# mega.net
KiCad netlist of a schematic drawn in EAGLE
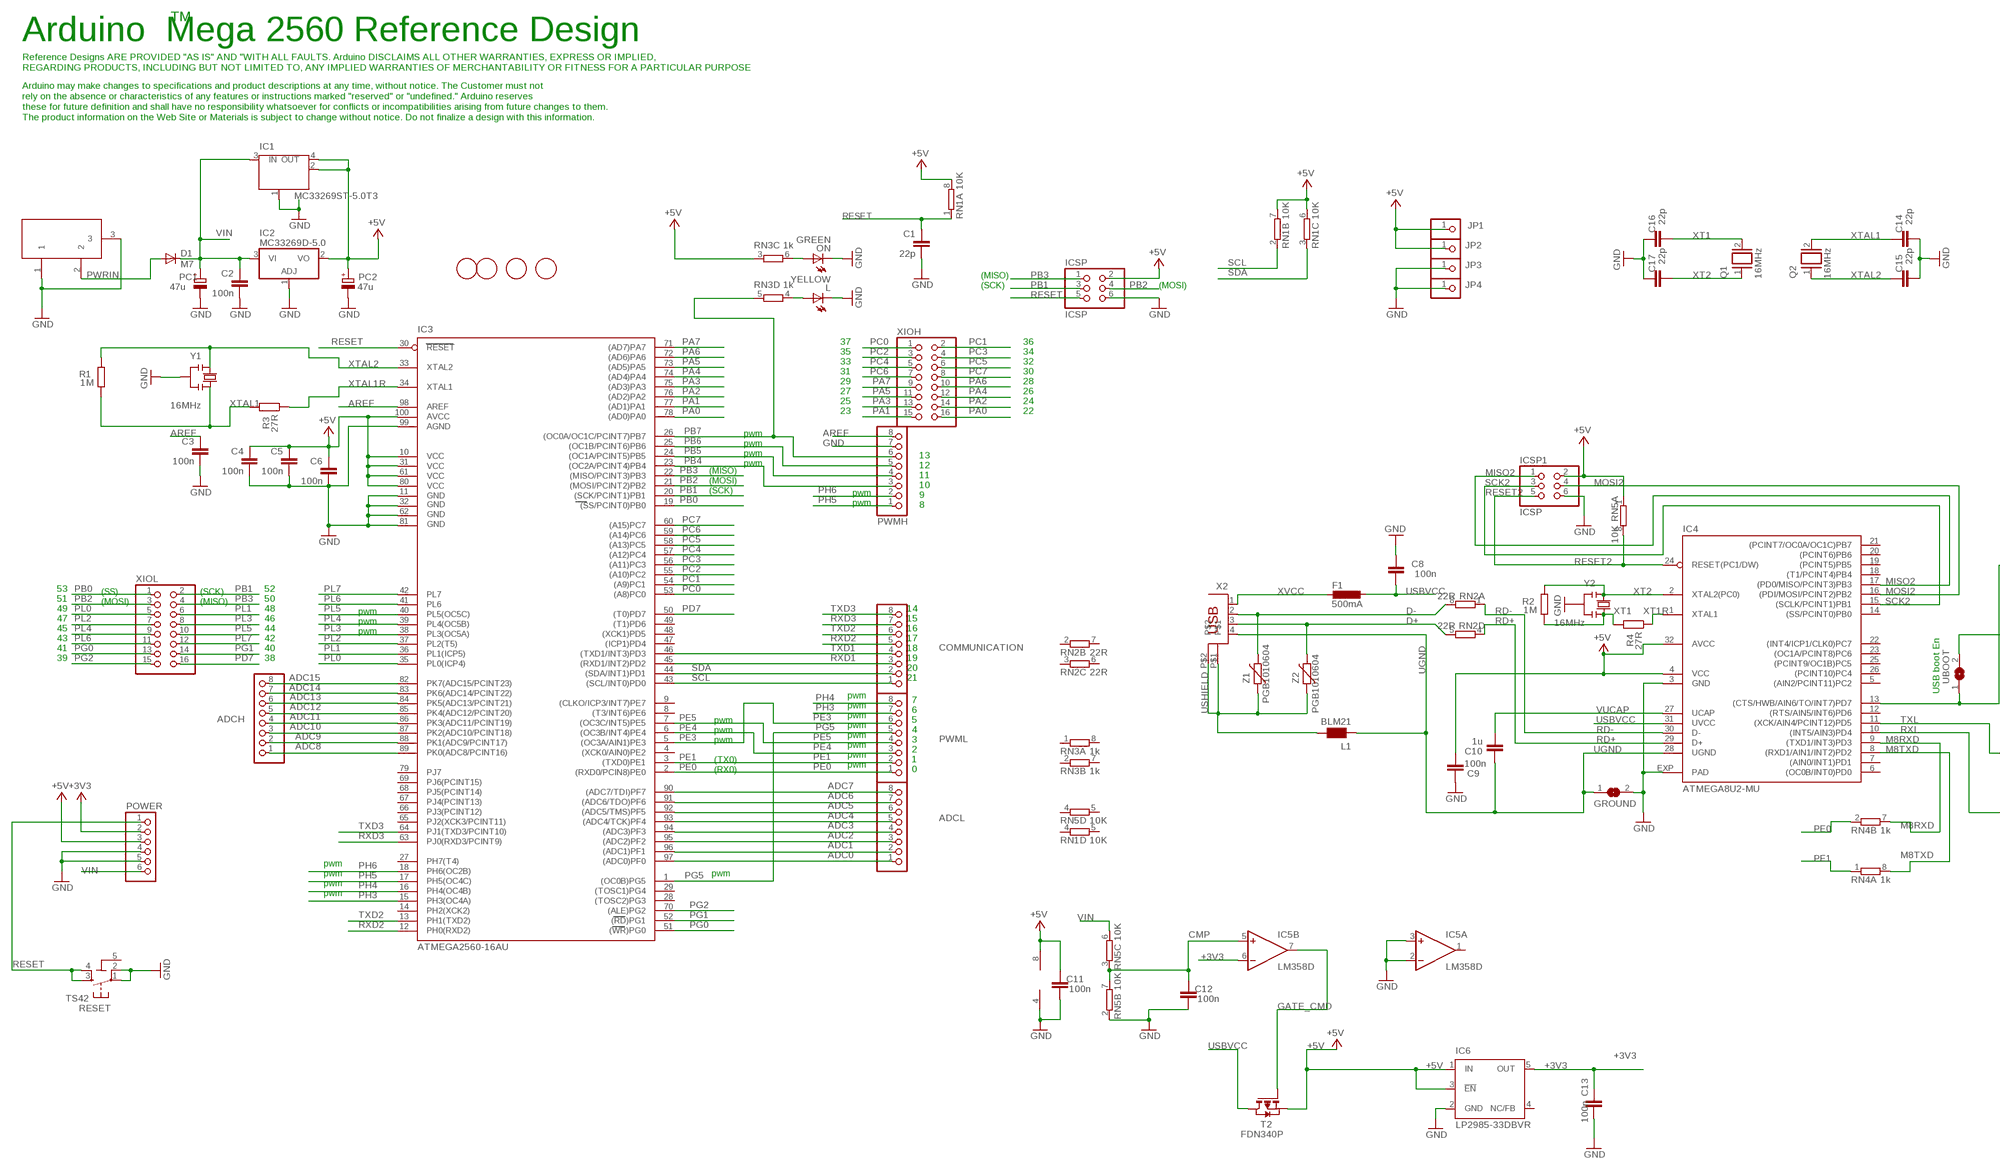
[diagram p0: schematic, sheet 1, part 1 of 2]
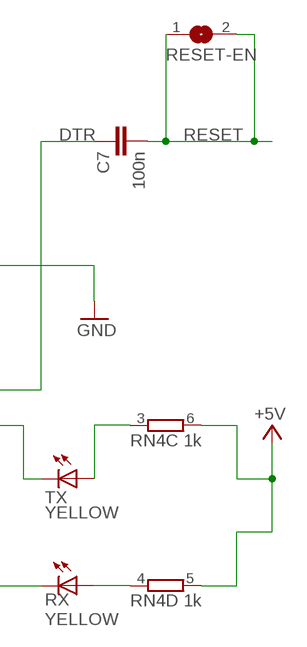
[diagram p1: schematic, sheet 1, part 2 of 2]

(export (version "E")
  (design (tool "Eeschema 10.0.6"))
  (components
    (comp (ref "ADCH")
      (value "PINHD-1X8")
      (footprint "eagle-import:1X08")
      (libsource (lib "eagle-import") (part "PINHD-1X8"))
    )
    (comp (ref "ADCL")
      (value "PINHD-1X8")
      (footprint "eagle-import:1X08")
      (libsource (lib "eagle-import") (part "PINHD-1X8"))
    )
    (comp (ref "C1")
      (value "22p")
      (footprint "eagle-import:C0603-ROUND")
      (libsource (lib "eagle-import") (part "C-EU0603-RND"))
    )
    (comp (ref "C2")
      (value "100n")
      (footprint "eagle-import:C0603-ROUND")
      (libsource (lib "eagle-import") (part "C-EU0603-RND"))
    )
    (comp (ref "C3")
      (value "100n")
      (footprint "eagle-import:C0603-ROUND")
      (libsource (lib "eagle-import") (part "C-EU0603-RND"))
    )
    (comp (ref "C4")
      (value "100n")
      (footprint "eagle-import:C0603-ROUND")
      (libsource (lib "eagle-import") (part "C-EU0603-RND"))
    )
    (comp (ref "C5")
      (value "100n")
      (footprint "eagle-import:C0603-ROUND")
      (libsource (lib "eagle-import") (part "C-EU0603-RND"))
    )
    (comp (ref "C6")
      (value "100n")
      (footprint "eagle-import:C0603-ROUND")
      (libsource (lib "eagle-import") (part "C-EU0603-RND"))
    )
    (comp (ref "C7")
      (value "100n")
      (footprint "eagle-import:C0603-ROUND")
      (libsource (lib "eagle-import") (part "C-EU0603-RND"))
    )
    (comp (ref "C8")
      (value "100n")
      (footprint "eagle-import:C0603")
      (libsource (lib "eagle-import") (part "rcl_C-EUC0603"))
    )
    (comp (ref "C9")
      (value "100n")
      (footprint "eagle-import:C0603-ROUND")
      (libsource (lib "eagle-import") (part "C-EU0603-RND"))
    )
    (comp (ref "C10")
      (value "1u")
      (footprint "eagle-import:C0603-ROUND")
      (libsource (lib "eagle-import") (part "C-EU0603-RND"))
    )
    (comp (ref "C11")
      (value "100n")
      (footprint "eagle-import:C0603")
      (libsource (lib "eagle-import") (part "rcl_C-EUC0603"))
    )
    (comp (ref "C12")
      (value "100n")
      (footprint "eagle-import:C0603-ROUND")
      (libsource (lib "eagle-import") (part "C-EU0603-RND"))
    )
    (comp (ref "C13")
      (value "100n")
      (footprint "eagle-import:C0603-ROUND")
      (libsource (lib "eagle-import") (part "C-EU0603-RND"))
    )
    (comp (ref "C14")
      (value "22p")
      (footprint "eagle-import:C0603-ROUND")
      (libsource (lib "eagle-import") (part "C-EU0603-RND"))
    )
    (comp (ref "C15")
      (value "22p")
      (footprint "eagle-import:C0603-ROUND")
      (libsource (lib "eagle-import") (part "C-EU0603-RND"))
    )
    (comp (ref "C16")
      (value "22p")
      (footprint "eagle-import:C0603-ROUND")
      (libsource (lib "eagle-import") (part "C-EU0603-RND"))
    )
    (comp (ref "C17")
      (value "22p")
      (footprint "eagle-import:C0603-ROUND")
      (libsource (lib "eagle-import") (part "C-EU0603-RND"))
    )
    (comp (ref "COMMUNICATION")
      (value "PINHD-1X8")
      (footprint "eagle-import:1X08")
      (libsource (lib "eagle-import") (part "PINHD-1X8"))
    )
    (comp (ref "D1")
      (value "M7")
      (footprint "eagle-import:SMB")
      (libsource (lib "eagle-import") (part "DIODE-SMB"))
    )
    (comp (ref "F1")
      (value "500mA")
      (footprint "eagle-import:L1812")
      (libsource (lib "eagle-import") (part "L-EUL1812"))
    )
    (comp (ref "GROUND")
      (value "SJ")
      (footprint "eagle-import:SJ")
      (libsource (lib "eagle-import") (part "SJ"))
    )
    (comp (ref "IC1")
      (value "MC33269ST-5.0T3")
      (footprint "eagle-import:SOT223")
      (libsource (lib "eagle-import") (part "MC33269ST-3.3T3"))
    )
    (comp (ref "IC2")
      (value "MC33269D-5.0")
      (footprint "eagle-import:DPACK")
      (libsource (lib "eagle-import") (part "MC33269?D-5.0"))
    )
    (comp (ref "IC3")
      (value "ATMEGA2560-16AU")
      (footprint "eagle-import:TQFP100")
      (libsource (lib "eagle-import") (part "ATMEGAAU1280-16"))
    )
    (comp (ref "IC4")
      (value "ATMEGA8U2-MU")
      (footprint "eagle-import:QFN32")
      (libsource (lib "eagle-import") (part "ATMEGA8U2-MU"))
    )
    (comp (ref "IC5")
      (value "LM358D")
      (footprint "eagle-import:SO08")
      (libsource (lib "eagle-import") (part "LM358D"))
    )
    (comp (ref "IC6")
      (value "LP2985-33DBVR")
      (footprint "eagle-import:SOT23-DBV")
      (libsource (lib "eagle-import") (part "TPS77033"))
    )
    (comp (ref "ICSP")
      (value "ICSP")
      (footprint "eagle-import:2X03")
      (libsource (lib "eagle-import") (part "PINHD-2X3"))
    )
    (comp (ref "ICSP1")
      (value "ICSP")
      (footprint "eagle-import:2X03")
      (libsource (lib "eagle-import") (part "PINHD-2X3"))
    )
    (comp (ref "JP1")
      (value "PINHD-1X1")
      (footprint "eagle-import:1X01")
      (libsource (lib "eagle-import") (part "PINHD-1X1"))
    )
    (comp (ref "JP2")
      (value "PINHD-1X1")
      (footprint "eagle-import:1X01")
      (libsource (lib "eagle-import") (part "PINHD-1X1"))
    )
    (comp (ref "JP3")
      (value "PINHD-1X1")
      (footprint "eagle-import:1X01")
      (libsource (lib "eagle-import") (part "PINHD-1X1"))
    )
    (comp (ref "JP4")
      (value "PINHD-1X1")
      (footprint "eagle-import:1X01")
      (libsource (lib "eagle-import") (part "PINHD-1X1"))
    )
    (comp (ref "L")
      (value "YELLOW")
      (footprint "eagle-import:CHIP-LED0805")
      (libsource (lib "eagle-import") (part "LEDCHIP-LED0805"))
    )
    (comp (ref "L1")
      (value "BLM21")
      (footprint "eagle-import:0805")
      (libsource (lib "eagle-import") (part "WE-CBF_0805"))
    )
    (comp (ref "ON")
      (value "GREEN")
      (footprint "eagle-import:CHIP-LED0805")
      (libsource (lib "eagle-import") (part "LEDCHIP-LED0805"))
    )
    (comp (ref "PC1")
      (value "47u")
      (footprint "eagle-import:PANASONIC_D")
      (libsource (lib "eagle-import") (part "CPOL-EUD"))
    )
    (comp (ref "PC2")
      (value "47u")
      (footprint "eagle-import:PANASONIC_D")
      (libsource (lib "eagle-import") (part "CPOL-EUD"))
    )
    (comp (ref "POWER")
      (value "PINHD-1X6")
      (footprint "eagle-import:1X06")
      (libsource (lib "eagle-import") (part "PINHD-1X6"))
    )
    (comp (ref "PWMH")
      (value "PINHD-1X8")
      (footprint "eagle-import:1X08")
      (libsource (lib "eagle-import") (part "PINHD-1X8"))
    )
    (comp (ref "PWML")
      (value "PINHD-1X8")
      (footprint "eagle-import:1X08")
      (libsource (lib "eagle-import") (part "PINHD-1X8"))
    )
    (comp (ref "Q1")
      (value "16MHz")
      (footprint "eagle-import:QS")
      (libsource (lib "eagle-import") (part "XTAL/S"))
    )
    (comp (ref "Q2")
      (value "16MHz")
      (footprint "eagle-import:QS")
      (libsource (lib "eagle-import") (part "XTAL/S"))
    )
    (comp (ref "R1")
      (value "1M")
      (footprint "eagle-import:R0603-ROUND")
      (libsource (lib "eagle-import") (part "R-EU_R0603"))
    )
    (comp (ref "R2")
      (value "1M")
      (footprint "eagle-import:R0603-ROUND")
      (libsource (lib "eagle-import") (part "R-EU_R0603"))
    )
    (comp (ref "R3")
      (value "27R")
      (footprint "eagle-import:R0603-ROUND")
      (libsource (lib "eagle-import") (part "R-EU_R0603"))
    )
    (comp (ref "R4")
      (value "27R")
      (footprint "eagle-import:R0603-ROUND")
      (libsource (lib "eagle-import") (part "R-EU_R0603"))
    )
    (comp (ref "RESET")
      (value "TS42")
      (footprint "eagle-import:TS42")
      (libsource (lib "eagle-import") (part "TS42"))
    )
    (comp (ref "RESET-EN")
      (value "SJ")
      (footprint "eagle-import:SJ")
      (libsource (lib "eagle-import") (part "SJ"))
    )
    (comp (ref "RN1")
      (value "10K")
      (footprint "eagle-import:CAT16")
      (libsource (lib "eagle-import") (part "4R-NCAT16"))
    )
    (comp (ref "RN2")
      (value "22R")
      (footprint "eagle-import:CAY16")
      (libsource (lib "eagle-import") (part "4R-NCAY16"))
    )
    (comp (ref "RN3")
      (value "1k")
      (footprint "eagle-import:CAY16")
      (libsource (lib "eagle-import") (part "4R-NCAY16"))
    )
    (comp (ref "RN4")
      (value "1k")
      (footprint "eagle-import:CAY16")
      (libsource (lib "eagle-import") (part "4R-NCAY16"))
    )
    (comp (ref "RN5")
      (value "10K")
      (footprint "eagle-import:CAT16")
      (libsource (lib "eagle-import") (part "4R-NCAT16"))
    )
    (comp (ref "RX")
      (value "YELLOW")
      (footprint "eagle-import:CHIP-LED0805")
      (libsource (lib "eagle-import") (part "LEDCHIP-LED0805"))
    )
    (comp (ref "T2")
      (value "FDN340P")
      (footprint "eagle-import:SOT-23")
      (libsource (lib "eagle-import") (part "PMOSSOT23"))
    )
    (comp (ref "TX")
      (value "YELLOW")
      (footprint "eagle-import:CHIP-LED0805")
      (libsource (lib "eagle-import") (part "LEDCHIP-LED0805"))
    )
    (comp (ref "U$2")
      (value "FIDUCIALMOUNT")
      (footprint "eagle-import:FIDUCIA-MOUNT")
      (libsource (lib "eagle-import") (part "FIDUCIALMOUNT"))
    )
    (comp (ref "U$3")
      (value "FIDUCIALMOUNT")
      (footprint "eagle-import:FIDUCIA-MOUNT")
      (libsource (lib "eagle-import") (part "FIDUCIALMOUNT"))
    )
    (comp (ref "U$4")
      (value "FIDUCIALMOUNT")
      (footprint "eagle-import:FIDUCIA-MOUNT")
      (libsource (lib "eagle-import") (part "FIDUCIALMOUNT"))
    )
    (comp (ref "U$5")
      (value "FIDUCIALMOUNT")
      (footprint "eagle-import:FIDUCIA-MOUNT")
      (libsource (lib "eagle-import") (part "FIDUCIALMOUNT"))
    )
    (comp (ref "UBOOT")
      (value "SJ")
      (footprint "eagle-import:SJ")
      (libsource (lib "eagle-import") (part "SJ"))
    )
    (comp (ref "X1")
      (value "DC21MMX")
      (footprint "eagle-import:DC-21MM")
      (libsource (lib "eagle-import") (part "DC21MMX"))
    )
    (comp (ref "X2")
      (value "PN61729")
      (footprint "eagle-import:PN61729")
      (libsource (lib "eagle-import") (part "PN61729"))
    )
    (comp (ref "XIOH")
      (value "PINHD-2X8")
      (footprint "eagle-import:2X08")
      (libsource (lib "eagle-import") (part "PINHD-2X8"))
    )
    (comp (ref "XIOL")
      (value "PINHD-2X8")
      (footprint "eagle-import:2X08")
      (libsource (lib "eagle-import") (part "PINHD-2X8"))
    )
    (comp (ref "Y1")
      (value "16MHz")
      (footprint "eagle-import:RESONATOR")
      (libsource (lib "eagle-import") (part "RESONATORMU"))
    )
    (comp (ref "Y2")
      (value "16MHz")
      (footprint "eagle-import:RESONATOR")
      (libsource (lib "eagle-import") (part "RESONATORMU"))
    )
    (comp (ref "Z1")
      (value "PGB1010604")
      (footprint "eagle-import:CT_CN0603")
      (libsource (lib "eagle-import") (part "VARISTORCN0603"))
    )
    (comp (ref "Z2")
      (value "PGB1010604")
      (footprint "eagle-import:CT_CN0603")
      (libsource (lib "eagle-import") (part "VARISTORCN0603"))
    )
  )
  (nets
    (net (code "1") (name "+3V3") (class "Default")
      (node (ref "C13") (pin "2") (pinfunction "2_2") (pintype "passive"))
      (node (ref "IC5") (pin "6") (pinfunction "-IN_6") (pintype "input"))
      (node (ref "IC6") (pin "5") (pinfunction "OUT_5") (pintype "passive"))
      (node (ref "POWER") (pin "2") (pinfunction "2_2") (pintype "passive"))
    )
    (net (code "2") (name "+5V") (class "Default")
      (node (ref "C11") (pin "2") (pinfunction "2_2") (pintype "passive"))
      (node (ref "C4") (pin "1") (pinfunction "1_1") (pintype "passive"))
      (node (ref "C5") (pin "1") (pinfunction "1_1") (pintype "passive"))
      (node (ref "C6") (pin "1") (pinfunction "1_1") (pintype "passive"))
      (node (ref "C9") (pin "1") (pinfunction "1_1") (pintype "passive"))
      (node (ref "IC1") (pin "2") (pinfunction "OUT_2") (pintype "passive"))
      (node (ref "IC1") (pin "4") (pinfunction "OUT_4") (pintype "passive"))
      (node (ref "IC2") (pin "2") (pinfunction "VO_2") (pintype "passive"))
      (node (ref "IC3") (pin "10") (pinfunction "VCC_10") (pintype "power_in"))
      (node (ref "IC3") (pin "100") (pinfunction "AVCC_100") (pintype "power_in"))
      (node (ref "IC3") (pin "31") (pinfunction "VCC1_31") (pintype "power_in"))
      (node (ref "IC3") (pin "61") (pinfunction "VCC2_61") (pintype "power_in"))
      (node (ref "IC3") (pin "80") (pinfunction "VCC3_80") (pintype "power_in"))
      (node (ref "IC4") (pin "32") (pinfunction "AVCC_32") (pintype "power_in"))
      (node (ref "IC4") (pin "4") (pinfunction "VCC_4") (pintype "power_in"))
      (node (ref "IC5") (pin "8") (pinfunction "V+_8") (pintype "power_in"))
      (node (ref "IC6") (pin "1") (pinfunction "IN_1") (pintype "input"))
      (node (ref "IC6") (pin "3") (pinfunction "~{EN}_3") (pintype "input"))
      (node (ref "ICSP") (pin "2") (pinfunction "2_2") (pintype "passive"))
      (node (ref "ICSP1") (pin "2") (pinfunction "2_2") (pintype "passive"))
      (node (ref "JP1") (pin "1") (pinfunction "1_1") (pintype "passive"))
      (node (ref "JP2") (pin "1") (pinfunction "1_1") (pintype "passive"))
      (node (ref "PC2") (pin "+") (pinfunction "+_+") (pintype "passive"))
      (node (ref "POWER") (pin "3") (pinfunction "3_3") (pintype "passive"))
      (node (ref "RN1") (pin "6") (pinfunction "2_6") (pintype "passive"))
      (node (ref "RN1") (pin "7") (pinfunction "2_7") (pintype "passive"))
      (node (ref "RN1") (pin "8") (pinfunction "2_8") (pintype "passive"))
      (node (ref "RN3") (pin "3") (pinfunction "1_3") (pintype "passive"))
      (node (ref "RN4") (pin "5") (pinfunction "2_5") (pintype "passive"))
      (node (ref "RN4") (pin "6") (pinfunction "2_6") (pintype "passive"))
      (node (ref "RN5") (pin "1") (pinfunction "1_1") (pintype "passive"))
      (node (ref "T2") (pin "2") (pinfunction "S_2") (pintype "passive"))
    )
    (net (code "3") (name "/5-GND") (class "Default")
      (node (ref "RESET") (pin "5") (pinfunction "5-GND_5") (pintype "power_in"))
    )
    (net (code "4") (name "/ADC0") (class "Default")
      (node (ref "ADCL") (pin "1") (pinfunction "1_1") (pintype "passive"))
      (node (ref "IC3") (pin "97") (pinfunction "(ADC0)PF0_97") (pintype "bidirectional"))
    )
    (net (code "5") (name "/ADC1") (class "Default")
      (node (ref "ADCL") (pin "2") (pinfunction "2_2") (pintype "passive"))
      (node (ref "IC3") (pin "96") (pinfunction "(ADC1)PF1_96") (pintype "bidirectional"))
    )
    (net (code "6") (name "/ADC2") (class "Default")
      (node (ref "ADCL") (pin "3") (pinfunction "3_3") (pintype "passive"))
      (node (ref "IC3") (pin "95") (pinfunction "(ADC2)PF2_95") (pintype "bidirectional"))
    )
    (net (code "7") (name "/ADC3") (class "Default")
      (node (ref "ADCL") (pin "4") (pinfunction "4_4") (pintype "passive"))
      (node (ref "IC3") (pin "94") (pinfunction "(ADC3)PF3_94") (pintype "bidirectional"))
    )
    (net (code "8") (name "/ADC4") (class "Default")
      (node (ref "ADCL") (pin "5") (pinfunction "5_5") (pintype "passive"))
      (node (ref "IC3") (pin "93") (pinfunction "(ADC4/TCK)PF4_93") (pintype "bidirectional"))
    )
    (net (code "9") (name "/ADC5") (class "Default")
      (node (ref "ADCL") (pin "6") (pinfunction "6_6") (pintype "passive"))
      (node (ref "IC3") (pin "92") (pinfunction "(ADC5/TMS)PF5_92") (pintype "bidirectional"))
    )
    (net (code "10") (name "/ADC6") (class "Default")
      (node (ref "ADCL") (pin "7") (pinfunction "7_7") (pintype "passive"))
      (node (ref "IC3") (pin "91") (pinfunction "(ADC6/TDO)PF6_91") (pintype "bidirectional"))
    )
    (net (code "11") (name "/ADC7") (class "Default")
      (node (ref "ADCL") (pin "8") (pinfunction "8_8") (pintype "passive"))
      (node (ref "IC3") (pin "90") (pinfunction "(ADC7/TDI)PF7_90") (pintype "bidirectional"))
    )
    (net (code "12") (name "/ADC8") (class "Default")
      (node (ref "ADCH") (pin "1") (pinfunction "1_1") (pintype "passive"))
      (node (ref "IC3") (pin "89") (pinfunction "PK0(ADC8/PCINT16)_89") (pintype "bidirectional"))
    )
    (net (code "13") (name "/ADC9") (class "Default")
      (node (ref "ADCH") (pin "2") (pinfunction "2_2") (pintype "passive"))
      (node (ref "IC3") (pin "88") (pinfunction "PK1(ADC9/PCINT17)_88") (pintype "bidirectional"))
    )
    (net (code "14") (name "/ADC10") (class "Default")
      (node (ref "ADCH") (pin "3") (pinfunction "3_3") (pintype "passive"))
      (node (ref "IC3") (pin "87") (pinfunction "PK2(ADC10/PCINT18)_87") (pintype "bidirectional"))
    )
    (net (code "15") (name "/ADC11") (class "Default")
      (node (ref "ADCH") (pin "4") (pinfunction "4_4") (pintype "passive"))
      (node (ref "IC3") (pin "86") (pinfunction "PK3(ADC11/PCINT19)_86") (pintype "bidirectional"))
    )
    (net (code "16") (name "/ADC12") (class "Default")
      (node (ref "ADCH") (pin "5") (pinfunction "5_5") (pintype "passive"))
      (node (ref "IC3") (pin "85") (pinfunction "PK4(ADC12/PCINT20)_85") (pintype "bidirectional"))
    )
    (net (code "17") (name "/ADC13") (class "Default")
      (node (ref "ADCH") (pin "6") (pinfunction "6_6") (pintype "passive"))
      (node (ref "IC3") (pin "84") (pinfunction "PK5(ADC13/PCINT21)_84") (pintype "bidirectional"))
    )
    (net (code "18") (name "/ADC14") (class "Default")
      (node (ref "ADCH") (pin "7") (pinfunction "7_7") (pintype "passive"))
      (node (ref "IC3") (pin "83") (pinfunction "PK6(ADC14/PCINT22)_83") (pintype "bidirectional"))
    )
    (net (code "19") (name "/ADC15") (class "Default")
      (node (ref "ADCH") (pin "8") (pinfunction "8_8") (pintype "passive"))
      (node (ref "IC3") (pin "82") (pinfunction "PK7(ADC15/PCINT23)_82") (pintype "bidirectional"))
    )
    (net (code "20") (name "/AREF") (class "Default")
      (node (ref "C3") (pin "1") (pinfunction "1_1") (pintype "passive"))
      (node (ref "IC3") (pin "98") (pinfunction "AREF_98") (pintype "bidirectional"))
      (node (ref "PWMH") (pin "8") (pinfunction "8_8") (pintype "passive"))
    )
    (net (code "21") (name "/CMP") (class "Default")
      (node (ref "C12") (pin "2") (pinfunction "2_2") (pintype "passive"))
      (node (ref "IC5") (pin "5") (pinfunction "+IN_5") (pintype "input"))
      (node (ref "RN5") (pin "3") (pinfunction "1_3") (pintype "passive"))
      (node (ref "RN5") (pin "7") (pinfunction "2_7") (pintype "passive"))
    )
    (net (code "22") (name "/D+") (class "Default")
      (node (ref "RN2") (pin "5") (pinfunction "2_5") (pintype "passive"))
      (node (ref "X2") (pin "3") (pinfunction "3_3") (pintype "bidirectional"))
      (node (ref "Z2") (pin "2") (pinfunction "2_2") (pintype "passive"))
    )
    (net (code "23") (name "/D-") (class "Default")
      (node (ref "RN2") (pin "8") (pinfunction "2_8") (pintype "passive"))
      (node (ref "X2") (pin "2") (pinfunction "2_2") (pintype "bidirectional"))
      (node (ref "Z1") (pin "2") (pinfunction "2_2") (pintype "passive"))
    )
    (net (code "24") (name "/DTR") (class "Default")
      (node (ref "C7") (pin "1") (pinfunction "1_1") (pintype "passive"))
      (node (ref "IC4") (pin "13") (pinfunction "(CTS/HWB/AIN6/TO/INT7)PD7_13") (pintype "bidirectional"))
      (node (ref "UBOOT") (pin "1") (pinfunction "1_1") (pintype "passive"))
    )
    (net (code "25") (name "/GATE_CMD") (class "Default")
      (node (ref "IC5") (pin "7") (pinfunction "OUT_7") (pintype "output"))
      (node (ref "T2") (pin "3") (pinfunction "G_3") (pintype "passive"))
    )
    (net (code "26") (name "/M8RXD") (class "Default")
      (node (ref "IC4") (pin "9") (pinfunction "(TXD1/INT3)PD3_9") (pintype "bidirectional"))
      (node (ref "RN4") (pin "7") (pinfunction "2_7") (pintype "passive"))
    )
    (net (code "27") (name "/M8TXD") (class "Default")
      (node (ref "IC4") (pin "8") (pinfunction "(RXD1/AIN1/INT2)PD2_8") (pintype "bidirectional"))
      (node (ref "RN4") (pin "8") (pinfunction "2_8") (pintype "passive"))
    )
    (net (code "28") (name "/MISO2") (class "Default")
      (node (ref "IC4") (pin "17") (pinfunction "(PD0/MISO/PCINT3)PB3_17") (pintype "bidirectional"))
      (node (ref "ICSP1") (pin "1") (pinfunction "1_1") (pintype "passive"))
    )
    (net (code "29") (name "/MOSI2") (class "Default")
      (node (ref "IC4") (pin "16") (pinfunction "(PDI/MOSI/PCINT2)PB2_16") (pintype "bidirectional"))
      (node (ref "ICSP1") (pin "4") (pinfunction "4_4") (pintype "passive"))
    )
    (net (code "30") (name "/PA0") (class "Default")
      (node (ref "IC3") (pin "78") (pinfunction "(AD0)PA0_78") (pintype "bidirectional"))
      (node (ref "XIOH") (pin "16") (pinfunction "16_16") (pintype "passive"))
    )
    (net (code "31") (name "/PA1") (class "Default")
      (node (ref "IC3") (pin "77") (pinfunction "(AD1)PA1_77") (pintype "bidirectional"))
      (node (ref "XIOH") (pin "15") (pinfunction "15_15") (pintype "passive"))
    )
    (net (code "32") (name "/PA2") (class "Default")
      (node (ref "IC3") (pin "76") (pinfunction "(AD2)PA2_76") (pintype "bidirectional"))
      (node (ref "XIOH") (pin "14") (pinfunction "14_14") (pintype "passive"))
    )
    (net (code "33") (name "/PA3") (class "Default")
      (node (ref "IC3") (pin "75") (pinfunction "(AD3)PA3_75") (pintype "bidirectional"))
      (node (ref "XIOH") (pin "13") (pinfunction "13_13") (pintype "passive"))
    )
    (net (code "34") (name "/PA4") (class "Default")
      (node (ref "IC3") (pin "74") (pinfunction "(AD4)PA4_74") (pintype "bidirectional"))
      (node (ref "XIOH") (pin "12") (pinfunction "12_12") (pintype "passive"))
    )
    (net (code "35") (name "/PA5") (class "Default")
      (node (ref "IC3") (pin "73") (pinfunction "(AD5)PA5_73") (pintype "bidirectional"))
      (node (ref "XIOH") (pin "11") (pinfunction "11_11") (pintype "passive"))
    )
    (net (code "36") (name "/PA6") (class "Default")
      (node (ref "IC3") (pin "72") (pinfunction "(AD6)PA6_72") (pintype "bidirectional"))
      (node (ref "XIOH") (pin "10") (pinfunction "10_10") (pintype "passive"))
    )
    (net (code "37") (name "/PA7") (class "Default")
      (node (ref "IC3") (pin "71") (pinfunction "(AD7)PA7_71") (pintype "bidirectional"))
      (node (ref "XIOH") (pin "9") (pinfunction "9_9") (pintype "passive"))
    )
    (net (code "38") (name "/PB0") (class "Default")
      (node (ref "IC3") (pin "19") (pinfunction "(SS/PCINT0)PB0_19") (pintype "bidirectional"))
      (node (ref "XIOL") (pin "1") (pinfunction "1_1") (pintype "passive"))
    )
    (net (code "39") (name "/PB1") (class "Default")
      (node (ref "IC3") (pin "20") (pinfunction "(SCK/PCINT1)PB1_20") (pintype "bidirectional"))
      (node (ref "ICSP") (pin "3") (pinfunction "3_3") (pintype "passive"))
      (node (ref "XIOL") (pin "2") (pinfunction "2_2") (pintype "passive"))
    )
    (net (code "40") (name "/PB2") (class "Default")
      (node (ref "IC3") (pin "21") (pinfunction "(MOSI/PCINT2)PB2_21") (pintype "bidirectional"))
      (node (ref "ICSP") (pin "4") (pinfunction "4_4") (pintype "passive"))
      (node (ref "XIOL") (pin "3") (pinfunction "3_3") (pintype "passive"))
    )
    (net (code "41") (name "/PB3") (class "Default")
      (node (ref "IC3") (pin "22") (pinfunction "(MISO/PCINT3)PB3_22") (pintype "bidirectional"))
      (node (ref "ICSP") (pin "1") (pinfunction "1_1") (pintype "passive"))
      (node (ref "XIOL") (pin "4") (pinfunction "4_4") (pintype "passive"))
    )
    (net (code "42") (name "/PB4") (class "Default")
      (node (ref "IC3") (pin "23") (pinfunction "(OC2A/PCINT4)PB4_23") (pintype "bidirectional"))
      (node (ref "PWMH") (pin "3") (pinfunction "3_3") (pintype "passive"))
    )
    (net (code "43") (name "/PB5") (class "Default")
      (node (ref "IC3") (pin "24") (pinfunction "(OC1A/PCINT5)PB5_24") (pintype "bidirectional"))
      (node (ref "PWMH") (pin "4") (pinfunction "4_4") (pintype "passive"))
    )
    (net (code "44") (name "/PB6") (class "Default")
      (node (ref "IC3") (pin "25") (pinfunction "(OC1B/PCINT6)PB6_25") (pintype "bidirectional"))
      (node (ref "PWMH") (pin "5") (pinfunction "5_5") (pintype "passive"))
    )
    (net (code "45") (name "/PB7") (class "Default")
      (node (ref "IC3") (pin "26") (pinfunction "(OC0A/OC1C/PCINT7)PB7_26") (pintype "bidirectional"))
      (node (ref "PWMH") (pin "6") (pinfunction "6_6") (pintype "passive"))
      (node (ref "RN3") (pin "5") (pinfunction "2_5") (pintype "passive"))
    )
    (net (code "46") (name "/PC0") (class "Default")
      (node (ref "IC3") (pin "53") (pinfunction "(A8)PC0_53") (pintype "bidirectional"))
      (node (ref "XIOH") (pin "1") (pinfunction "1_1") (pintype "passive"))
    )
    (net (code "47") (name "/PC1") (class "Default")
      (node (ref "IC3") (pin "54") (pinfunction "(A9)PC1_54") (pintype "bidirectional"))
      (node (ref "XIOH") (pin "2") (pinfunction "2_2") (pintype "passive"))
    )
    (net (code "48") (name "/PC2") (class "Default")
      (node (ref "IC3") (pin "55") (pinfunction "(A10)PC2_55") (pintype "bidirectional"))
      (node (ref "XIOH") (pin "3") (pinfunction "3_3") (pintype "passive"))
    )
    (net (code "49") (name "/PC3") (class "Default")
      (node (ref "IC3") (pin "56") (pinfunction "(A11)PC3_56") (pintype "bidirectional"))
      (node (ref "XIOH") (pin "4") (pinfunction "4_4") (pintype "passive"))
    )
    (net (code "50") (name "/PC4") (class "Default")
      (node (ref "IC3") (pin "57") (pinfunction "(A12)PC4_57") (pintype "bidirectional"))
      (node (ref "XIOH") (pin "5") (pinfunction "5_5") (pintype "passive"))
    )
    (net (code "51") (name "/PC5") (class "Default")
      (node (ref "IC3") (pin "58") (pinfunction "(A13)PC5_58") (pintype "bidirectional"))
      (node (ref "XIOH") (pin "6") (pinfunction "6_6") (pintype "passive"))
    )
    (net (code "52") (name "/PC6") (class "Default")
      (node (ref "IC3") (pin "59") (pinfunction "(A14)PC6_59") (pintype "bidirectional"))
      (node (ref "XIOH") (pin "7") (pinfunction "7_7") (pintype "passive"))
    )
    (net (code "53") (name "/PC7") (class "Default")
      (node (ref "IC3") (pin "60") (pinfunction "(A15)PC7_60") (pintype "bidirectional"))
      (node (ref "XIOH") (pin "8") (pinfunction "8_8") (pintype "passive"))
    )
    (net (code "54") (name "/PD7") (class "Default")
      (node (ref "IC3") (pin "50") (pinfunction "(T0)PD7_50") (pintype "bidirectional"))
      (node (ref "XIOL") (pin "16") (pinfunction "16_16") (pintype "passive"))
    )
    (net (code "55") (name "/PE0") (class "Default")
      (node (ref "IC3") (pin "2") (pinfunction "(RXD0/PCIN8)PE0_2") (pintype "bidirectional"))
      (node (ref "PWML") (pin "1") (pinfunction "1_1") (pintype "passive"))
      (node (ref "RN4") (pin "2") (pinfunction "1_2") (pintype "passive"))
    )
    (net (code "56") (name "/PE1") (class "Default")
      (node (ref "IC3") (pin "3") (pinfunction "(TXD0)PE1_3") (pintype "bidirectional"))
      (node (ref "PWML") (pin "2") (pinfunction "2_2") (pintype "passive"))
      (node (ref "RN4") (pin "1") (pinfunction "1_1") (pintype "passive"))
    )
    (net (code "57") (name "/PE3") (class "Default")
      (node (ref "IC3") (pin "5") (pinfunction "(OC3A/AIN1)PE3_5") (pintype "bidirectional"))
      (node (ref "PWML") (pin "6") (pinfunction "6_6") (pintype "passive"))
    )
    (net (code "58") (name "/PE4") (class "Default")
      (node (ref "IC3") (pin "6") (pinfunction "(OC3B/INT4)PE4_6") (pintype "bidirectional"))
      (node (ref "PWML") (pin "3") (pinfunction "3_3") (pintype "passive"))
    )
    (net (code "59") (name "/PE5") (class "Default")
      (node (ref "IC3") (pin "7") (pinfunction "(OC3C/INT5)PE5_7") (pintype "bidirectional"))
      (node (ref "PWML") (pin "4") (pinfunction "4_4") (pintype "passive"))
    )
    (net (code "60") (name "/PG0") (class "Default")
      (node (ref "IC3") (pin "51") (pinfunction "(WR)PG0_51") (pintype "bidirectional"))
      (node (ref "XIOL") (pin "13") (pinfunction "13_13") (pintype "passive"))
    )
    (net (code "61") (name "/PG1") (class "Default")
      (node (ref "IC3") (pin "52") (pinfunction "(RD)PG1_52") (pintype "bidirectional"))
      (node (ref "XIOL") (pin "14") (pinfunction "14_14") (pintype "passive"))
    )
    (net (code "62") (name "/PG2") (class "Default")
      (node (ref "IC3") (pin "70") (pinfunction "(ALE)PG2_70") (pintype "bidirectional"))
      (node (ref "XIOL") (pin "15") (pinfunction "15_15") (pintype "passive"))
    )
    (net (code "63") (name "/PG5") (class "Default")
      (node (ref "IC3") (pin "1") (pinfunction "(OC0B)PG5_1") (pintype "bidirectional"))
      (node (ref "PWML") (pin "5") (pinfunction "5_5") (pintype "passive"))
    )
    (net (code "64") (name "/PH3") (class "Default")
      (node (ref "IC3") (pin "15") (pinfunction "PH3(OC4A)_15") (pintype "bidirectional"))
      (node (ref "PWML") (pin "7") (pinfunction "7_7") (pintype "passive"))
    )
    (net (code "65") (name "/PH4") (class "Default")
      (node (ref "IC3") (pin "16") (pinfunction "PH4(OC4B)_16") (pintype "bidirectional"))
      (node (ref "PWML") (pin "8") (pinfunction "8_8") (pintype "passive"))
    )
    (net (code "66") (name "/PH5") (class "Default")
      (node (ref "IC3") (pin "17") (pinfunction "PH5(OC4C)_17") (pintype "bidirectional"))
      (node (ref "PWMH") (pin "1") (pinfunction "1_1") (pintype "passive"))
    )
    (net (code "67") (name "/PH6") (class "Default")
      (node (ref "IC3") (pin "18") (pinfunction "PH6(OC2B)_18") (pintype "bidirectional"))
      (node (ref "PWMH") (pin "2") (pinfunction "2_2") (pintype "passive"))
    )
    (net (code "68") (name "/PL0") (class "Default")
      (node (ref "IC3") (pin "35") (pinfunction "PL0(ICP4)_35") (pintype "bidirectional"))
      (node (ref "XIOL") (pin "5") (pinfunction "5_5") (pintype "passive"))
    )
    (net (code "69") (name "/PL1") (class "Default")
      (node (ref "IC3") (pin "36") (pinfunction "PL1(ICP5)_36") (pintype "bidirectional"))
      (node (ref "XIOL") (pin "6") (pinfunction "6_6") (pintype "passive"))
    )
    (net (code "70") (name "/PL2") (class "Default")
      (node (ref "IC3") (pin "37") (pinfunction "PL2(T5)_37") (pintype "bidirectional"))
      (node (ref "XIOL") (pin "7") (pinfunction "7_7") (pintype "passive"))
    )
    (net (code "71") (name "/PL3") (class "Default")
      (node (ref "IC3") (pin "38") (pinfunction "PL3(OC5A)_38") (pintype "bidirectional"))
      (node (ref "XIOL") (pin "8") (pinfunction "8_8") (pintype "passive"))
    )
    (net (code "72") (name "/PL4") (class "Default")
      (node (ref "IC3") (pin "39") (pinfunction "PL4(OC5B)_39") (pintype "bidirectional"))
      (node (ref "XIOL") (pin "9") (pinfunction "9_9") (pintype "passive"))
    )
    (net (code "73") (name "/PL5") (class "Default")
      (node (ref "IC3") (pin "40") (pinfunction "PL5(OC5C)_40") (pintype "bidirectional"))
      (node (ref "XIOL") (pin "10") (pinfunction "10_10") (pintype "passive"))
    )
    (net (code "74") (name "/PL6") (class "Default")
      (node (ref "IC3") (pin "41") (pinfunction "PL6_41") (pintype "bidirectional"))
      (node (ref "XIOL") (pin "11") (pinfunction "11_11") (pintype "passive"))
    )
    (net (code "75") (name "/PL7") (class "Default")
      (node (ref "IC3") (pin "42") (pinfunction "PL7_42") (pintype "bidirectional"))
      (node (ref "XIOL") (pin "12") (pinfunction "12_12") (pintype "passive"))
    )
    (net (code "76") (name "/PWRIN") (class "Default")
      (node (ref "D1") (pin "A") (pinfunction "A_A") (pintype "passive"))
      (node (ref "X1") (pin "2") (pinfunction "2_2") (pintype "power_in"))
    )
    (net (code "77") (name "/RD+") (class "Default")
      (node (ref "IC4") (pin "29") (pinfunction "D+_29") (pintype "bidirectional"))
      (node (ref "RN2") (pin "4") (pinfunction "1_4") (pintype "passive"))
    )
    (net (code "78") (name "/RD-") (class "Default")
      (node (ref "IC4") (pin "30") (pinfunction "D-_30") (pintype "bidirectional"))
      (node (ref "RN2") (pin "1") (pinfunction "1_1") (pintype "passive"))
    )
    (net (code "79") (name "/RESET") (class "Default")
      (node (ref "C1") (pin "1") (pinfunction "1_1") (pintype "passive"))
      (node (ref "C7") (pin "2") (pinfunction "2_2") (pintype "passive"))
      (node (ref "IC3") (pin "30") (pinfunction "RESET_30") (pintype "input"))
      (node (ref "ICSP") (pin "5") (pinfunction "5_5") (pintype "passive"))
      (node (ref "POWER") (pin "1") (pinfunction "1_1") (pintype "passive"))
      (node (ref "RESET") (pin "3") (pinfunction "3_3") (pintype "passive"))
      (node (ref "RESET") (pin "4") (pinfunction "4_4") (pintype "passive"))
      (node (ref "RESET-EN") (pin "1") (pinfunction "1_1") (pintype "passive"))
      (node (ref "RESET-EN") (pin "2") (pinfunction "2_2") (pintype "passive"))
      (node (ref "RN1") (pin "1") (pinfunction "1_1") (pintype "passive"))
    )
    (net (code "80") (name "/RESET2") (class "Default")
      (node (ref "IC4") (pin "24") (pinfunction "RESET(PC1/DW)_24") (pintype "input"))
      (node (ref "ICSP1") (pin "5") (pinfunction "5_5") (pintype "passive"))
      (node (ref "RN5") (pin "8") (pinfunction "2_8") (pintype "passive"))
    )
    (net (code "81") (name "/RXD1") (class "Default")
      (node (ref "COMMUNICATION") (pin "3") (pinfunction "3_3") (pintype "passive"))
      (node (ref "IC3") (pin "45") (pinfunction "(RXD1/INT2)PD2_45") (pintype "bidirectional"))
    )
    (net (code "82") (name "/RXD2") (class "Default")
      (node (ref "COMMUNICATION") (pin "5") (pinfunction "5_5") (pintype "passive"))
      (node (ref "IC3") (pin "12") (pinfunction "PH0(RXD2)_12") (pintype "bidirectional"))
    )
    (net (code "83") (name "/RXD3") (class "Default")
      (node (ref "COMMUNICATION") (pin "7") (pinfunction "7_7") (pintype "passive"))
      (node (ref "IC3") (pin "63") (pinfunction "PJ0(RXD3/PCINT9)_63") (pintype "bidirectional"))
    )
    (net (code "84") (name "/RXL") (class "Default")
      (node (ref "IC4") (pin "10") (pinfunction "(INT5/AIN3)PD4_10") (pintype "bidirectional"))
      (node (ref "RX") (pin "C") (pinfunction "C_C") (pintype "passive"))
    )
    (net (code "85") (name "/SCK2") (class "Default")
      (node (ref "IC4") (pin "15") (pinfunction "(SCLK/PCINT1)PB1_15") (pintype "bidirectional"))
      (node (ref "ICSP1") (pin "3") (pinfunction "3_3") (pintype "passive"))
    )
    (net (code "86") (name "/SCL") (class "Default")
      (node (ref "COMMUNICATION") (pin "1") (pinfunction "1_1") (pintype "passive"))
      (node (ref "IC3") (pin "43") (pinfunction "(SCL/INT0)PD0_43") (pintype "bidirectional"))
      (node (ref "RN1") (pin "2") (pinfunction "1_2") (pintype "passive"))
    )
    (net (code "87") (name "/SDA") (class "Default")
      (node (ref "COMMUNICATION") (pin "2") (pinfunction "2_2") (pintype "passive"))
      (node (ref "IC3") (pin "44") (pinfunction "(SDA/INT1)PD1_44") (pintype "bidirectional"))
      (node (ref "RN1") (pin "3") (pinfunction "1_3") (pintype "passive"))
    )
    (net (code "88") (name "/TXD1") (class "Default")
      (node (ref "COMMUNICATION") (pin "4") (pinfunction "4_4") (pintype "passive"))
      (node (ref "IC3") (pin "46") (pinfunction "(TXD1/INT3)PD3_46") (pintype "bidirectional"))
    )
    (net (code "89") (name "/TXD2") (class "Default")
      (node (ref "COMMUNICATION") (pin "6") (pinfunction "6_6") (pintype "passive"))
      (node (ref "IC3") (pin "13") (pinfunction "PH1(TXD2)_13") (pintype "bidirectional"))
    )
    (net (code "90") (name "/TXD3") (class "Default")
      (node (ref "COMMUNICATION") (pin "8") (pinfunction "8_8") (pintype "passive"))
      (node (ref "IC3") (pin "64") (pinfunction "PJ1(TXD3/PCINT10)_64") (pintype "bidirectional"))
    )
    (net (code "91") (name "/TXL") (class "Default")
      (node (ref "IC4") (pin "11") (pinfunction "(XCK/AIN4/PCINT12)PD5_11") (pintype "bidirectional"))
      (node (ref "TX") (pin "C") (pinfunction "C_C") (pintype "passive"))
    )
    (net (code "92") (name "/UGND") (class "Default")
      (node (ref "C10") (pin "2") (pinfunction "2_2") (pintype "passive"))
      (node (ref "GROUND") (pin "1") (pinfunction "1_1") (pintype "passive"))
      (node (ref "IC4") (pin "28") (pinfunction "UGND_28") (pintype "power_in"))
      (node (ref "L1") (pin "1") (pinfunction "1_1") (pintype "passive"))
      (node (ref "X2") (pin "4") (pinfunction "4_4") (pintype "bidirectional"))
    )
    (net (code "93") (name "/USBVCC") (class "Default")
      (node (ref "C8") (pin "1") (pinfunction "1_1") (pintype "passive"))
      (node (ref "F1") (pin "1") (pinfunction "1_1") (pintype "passive"))
      (node (ref "IC4") (pin "31") (pinfunction "UVCC_31") (pintype "power_in"))
      (node (ref "T2") (pin "1") (pinfunction "D_1") (pintype "passive"))
    )
    (net (code "94") (name "/USHIELD") (class "Default")
      (node (ref "L1") (pin "2") (pinfunction "2_2") (pintype "passive"))
      (node (ref "X2") (pin "P$1") (pinfunction "P$1_P$1") (pintype "bidirectional"))
      (node (ref "X2") (pin "P$2") (pinfunction "P$2_P$2") (pintype "bidirectional"))
      (node (ref "Z1") (pin "1") (pinfunction "1_1") (pintype "passive"))
      (node (ref "Z2") (pin "1") (pinfunction "1_1") (pintype "passive"))
    )
    (net (code "95") (name "/VIN") (class "Default")
      (node (ref "C2") (pin "1") (pinfunction "1_1") (pintype "passive"))
      (node (ref "D1") (pin "C") (pinfunction "C_C") (pintype "passive"))
      (node (ref "IC1") (pin "3") (pinfunction "IN_3") (pintype "input"))
      (node (ref "IC2") (pin "3") (pinfunction "VI_3") (pintype "input"))
      (node (ref "PC1") (pin "+") (pinfunction "+_+") (pintype "passive"))
      (node (ref "POWER") (pin "6") (pinfunction "6_6") (pintype "passive"))
      (node (ref "RN5") (pin "6") (pinfunction "2_6") (pintype "passive"))
    )
    (net (code "96") (name "/VUCAP") (class "Default")
      (node (ref "C10") (pin "1") (pinfunction "1_1") (pintype "passive"))
      (node (ref "IC4") (pin "27") (pinfunction "UCAP_27") (pintype "passive"))
    )
    (net (code "97") (name "/XT1") (class "Default")
      (node (ref "C16") (pin "1") (pinfunction "1_1") (pintype "passive"))
      (node (ref "Q1") (pin "2") (pinfunction "2_2") (pintype "passive"))
      (node (ref "R2") (pin "1") (pinfunction "1_1") (pintype "passive"))
      (node (ref "R4") (pin "2") (pinfunction "2_2") (pintype "passive"))
      (node (ref "Y2") (pin "3") (pinfunction "3_3") (pintype "passive"))
    )
    (net (code "98") (name "/XT1R") (class "Default")
      (node (ref "IC4") (pin "1") (pinfunction "XTAL1_1") (pintype "bidirectional"))
      (node (ref "R4") (pin "1") (pinfunction "1_1") (pintype "passive"))
    )
    (net (code "99") (name "/XT2") (class "Default")
      (node (ref "C17") (pin "1") (pinfunction "1_1") (pintype "passive"))
      (node (ref "IC4") (pin "2") (pinfunction "XTAL2(PC0)_2") (pintype "bidirectional"))
      (node (ref "Q1") (pin "1") (pinfunction "1_1") (pintype "passive"))
      (node (ref "R2") (pin "2") (pinfunction "2_2") (pintype "passive"))
      (node (ref "Y2") (pin "1") (pinfunction "1_1") (pintype "passive"))
    )
    (net (code "100") (name "/XTAL1") (class "Default")
      (node (ref "C14") (pin "2") (pinfunction "2_2") (pintype "passive"))
      (node (ref "Q2") (pin "2") (pinfunction "2_2") (pintype "passive"))
      (node (ref "R1") (pin "1") (pinfunction "1_1") (pintype "passive"))
      (node (ref "R3") (pin "2") (pinfunction "2_2") (pintype "passive"))
      (node (ref "Y1") (pin "3") (pinfunction "3_3") (pintype "passive"))
    )
    (net (code "101") (name "/XTAL1R") (class "Default")
      (node (ref "IC3") (pin "34") (pinfunction "XTAL1_34") (pintype "input"))
      (node (ref "R3") (pin "1") (pinfunction "1_1") (pintype "passive"))
    )
    (net (code "102") (name "/XTAL2") (class "Default")
      (node (ref "C15") (pin "2") (pinfunction "2_2") (pintype "passive"))
      (node (ref "IC3") (pin "33") (pinfunction "XTAL2_33") (pintype "output"))
      (node (ref "Q2") (pin "1") (pinfunction "1_1") (pintype "passive"))
      (node (ref "R1") (pin "2") (pinfunction "2_2") (pintype "passive"))
      (node (ref "Y1") (pin "1") (pinfunction "1_1") (pintype "passive"))
    )
    (net (code "103") (name "/XVCC") (class "Default")
      (node (ref "F1") (pin "2") (pinfunction "2_2") (pintype "passive"))
      (node (ref "X2") (pin "1") (pinfunction "1_1") (pintype "bidirectional"))
    )
    (net (code "104") (name "GND") (class "Default")
      (node (ref "C1") (pin "2") (pinfunction "2_2") (pintype "passive"))
      (node (ref "C11") (pin "1") (pinfunction "1_1") (pintype "passive"))
      (node (ref "C12") (pin "1") (pinfunction "1_1") (pintype "passive"))
      (node (ref "C13") (pin "1") (pinfunction "1_1") (pintype "passive"))
      (node (ref "C14") (pin "1") (pinfunction "1_1") (pintype "passive"))
      (node (ref "C15") (pin "1") (pinfunction "1_1") (pintype "passive"))
      (node (ref "C16") (pin "2") (pinfunction "2_2") (pintype "passive"))
      (node (ref "C17") (pin "2") (pinfunction "2_2") (pintype "passive"))
      (node (ref "C2") (pin "2") (pinfunction "2_2") (pintype "passive"))
      (node (ref "C3") (pin "2") (pinfunction "2_2") (pintype "passive"))
      (node (ref "C4") (pin "2") (pinfunction "2_2") (pintype "passive"))
      (node (ref "C5") (pin "2") (pinfunction "2_2") (pintype "passive"))
      (node (ref "C6") (pin "2") (pinfunction "2_2") (pintype "passive"))
      (node (ref "C8") (pin "2") (pinfunction "2_2") (pintype "passive"))
      (node (ref "C9") (pin "2") (pinfunction "2_2") (pintype "passive"))
      (node (ref "GROUND") (pin "2") (pinfunction "2_2") (pintype "passive"))
      (node (ref "IC1") (pin "1") (pinfunction "GND/ADJ_1") (pintype "input"))
      (node (ref "IC2") (pin "1") (pinfunction "ADJ_1") (pintype "input"))
      (node (ref "IC3") (pin "11") (pinfunction "GND_11") (pintype "power_in"))
      (node (ref "IC3") (pin "32") (pinfunction "GND1_32") (pintype "power_in"))
      (node (ref "IC3") (pin "62") (pinfunction "GND2_62") (pintype "power_in"))
      (node (ref "IC3") (pin "81") (pinfunction "GND3_81") (pintype "power_in"))
      (node (ref "IC3") (pin "99") (pinfunction "AGND_99") (pintype "power_in"))
      (node (ref "IC4") (pin "3") (pinfunction "GND_3") (pintype "power_in"))
      (node (ref "IC4") (pin "EXP") (pinfunction "PAD_EXP") (pintype "power_in"))
      (node (ref "IC5") (pin "2") (pinfunction "-IN_2") (pintype "input"))
      (node (ref "IC5") (pin "3") (pinfunction "+IN_3") (pintype "input"))
      (node (ref "IC5") (pin "4") (pinfunction "V-_4") (pintype "power_in"))
      (node (ref "IC6") (pin "2") (pinfunction "GND_2") (pintype "power_in"))
      (node (ref "ICSP") (pin "6") (pinfunction "6_6") (pintype "passive"))
      (node (ref "ICSP1") (pin "6") (pinfunction "6_6") (pintype "passive"))
      (node (ref "JP3") (pin "1") (pinfunction "1_1") (pintype "passive"))
      (node (ref "JP4") (pin "1") (pinfunction "1_1") (pintype "passive"))
      (node (ref "L") (pin "C") (pinfunction "C_C") (pintype "passive"))
      (node (ref "ON") (pin "C") (pinfunction "C_C") (pintype "passive"))
      (node (ref "PC1") (pin "-") (pinfunction "-_-") (pintype "passive"))
      (node (ref "PC2") (pin "-") (pinfunction "-_-") (pintype "passive"))
      (node (ref "POWER") (pin "4") (pinfunction "4_4") (pintype "passive"))
      (node (ref "POWER") (pin "5") (pinfunction "5_5") (pintype "passive"))
      (node (ref "PWMH") (pin "7") (pinfunction "7_7") (pintype "passive"))
      (node (ref "RESET") (pin "1") (pinfunction "1_1") (pintype "passive"))
      (node (ref "RESET") (pin "2") (pinfunction "2_2") (pintype "passive"))
      (node (ref "RN5") (pin "2") (pinfunction "1_2") (pintype "passive"))
      (node (ref "UBOOT") (pin "2") (pinfunction "2_2") (pintype "passive"))
      (node (ref "X1") (pin "1") (pinfunction "1_1") (pintype "power_in"))
      (node (ref "X1") (pin "3") (pinfunction "3_3") (pintype "power_in"))
      (node (ref "Y1") (pin "2") (pinfunction "2_2") (pintype "passive"))
      (node (ref "Y2") (pin "2") (pinfunction "2_2") (pintype "passive"))
    )
    (net (code "105") (name "Net-(RN3C-2)") (class "Default")
      (node (ref "ON") (pin "A") (pinfunction "A_A") (pintype "passive"))
      (node (ref "RN3") (pin "6") (pinfunction "2_6") (pintype "passive"))
    )
    (net (code "106") (name "Net-(RN3D-1)") (class "Default")
      (node (ref "L") (pin "A") (pinfunction "A_A") (pintype "passive"))
      (node (ref "RN3") (pin "4") (pinfunction "1_4") (pintype "passive"))
    )
    (net (code "107") (name "Net-(RN4C-1)") (class "Default")
      (node (ref "RN4") (pin "3") (pinfunction "1_3") (pintype "passive"))
      (node (ref "TX") (pin "A") (pinfunction "A_A") (pintype "passive"))
    )
    (net (code "108") (name "Net-(RN4D-1)") (class "Default")
      (node (ref "RN4") (pin "4") (pinfunction "1_4") (pintype "passive"))
      (node (ref "RX") (pin "A") (pinfunction "A_A") (pintype "passive"))
    )
    (net (code "109") (name "unconnected-(IC3-(CLKO{slash}ICP3{slash}INT7)PE7-Pad9)") (class "Default")
      (node (ref "IC3") (pin "9") (pinfunction "(CLKO/ICP3/INT7)PE7_9") (pintype "bidirectional"))
    )
    (net (code "110") (name "unconnected-(IC3-(ICP1)PD4-Pad47)") (class "Default")
      (node (ref "IC3") (pin "47") (pinfunction "(ICP1)PD4_47") (pintype "bidirectional"))
    )
    (net (code "111") (name "unconnected-(IC3-(T1)PD6-Pad49)") (class "Default")
      (node (ref "IC3") (pin "49") (pinfunction "(T1)PD6_49") (pintype "bidirectional"))
    )
    (net (code "112") (name "unconnected-(IC3-(T3{slash}INT6)PE6-Pad8)") (class "Default")
      (node (ref "IC3") (pin "8") (pinfunction "(T3/INT6)PE6_8") (pintype "bidirectional"))
    )
    (net (code "113") (name "unconnected-(IC3-(TOSC1)PG4-Pad29)") (class "Default")
      (node (ref "IC3") (pin "29") (pinfunction "(TOSC1)PG4_29") (pintype "bidirectional"))
    )
    (net (code "114") (name "unconnected-(IC3-(TOSC2)PG3-Pad28)") (class "Default")
      (node (ref "IC3") (pin "28") (pinfunction "(TOSC2)PG3_28") (pintype "bidirectional"))
    )
    (net (code "115") (name "unconnected-(IC3-(XCK0{slash}AIN0)PE2-Pad4)") (class "Default")
      (node (ref "IC3") (pin "4") (pinfunction "(XCK0/AIN0)PE2_4") (pintype "bidirectional"))
    )
    (net (code "116") (name "unconnected-(IC3-(XCK1)PD5-Pad48)") (class "Default")
      (node (ref "IC3") (pin "48") (pinfunction "(XCK1)PD5_48") (pintype "bidirectional"))
    )
    (net (code "117") (name "unconnected-(IC3-PH2(XCK2)-Pad14)") (class "Default")
      (node (ref "IC3") (pin "14") (pinfunction "PH2(XCK2)_14") (pintype "bidirectional"))
    )
    (net (code "118") (name "unconnected-(IC3-PH7(T4)-Pad27)") (class "Default")
      (node (ref "IC3") (pin "27") (pinfunction "PH7(T4)_27") (pintype "bidirectional"))
    )
    (net (code "119") (name "unconnected-(IC3-PJ2(XCK3{slash}PCINT11)-Pad65)") (class "Default")
      (node (ref "IC3") (pin "65") (pinfunction "PJ2(XCK3/PCINT11)_65") (pintype "bidirectional"))
    )
    (net (code "120") (name "unconnected-(IC3-PJ3(PCINT12)-Pad66)") (class "Default")
      (node (ref "IC3") (pin "66") (pinfunction "PJ3(PCINT12)_66") (pintype "bidirectional"))
    )
    (net (code "121") (name "unconnected-(IC3-PJ4(PCINT13)-Pad67)") (class "Default")
      (node (ref "IC3") (pin "67") (pinfunction "PJ4(PCINT13)_67") (pintype "bidirectional"))
    )
    (net (code "122") (name "unconnected-(IC3-PJ5(PCINT14)-Pad68)") (class "Default")
      (node (ref "IC3") (pin "68") (pinfunction "PJ5(PCINT14)_68") (pintype "bidirectional"))
    )
    (net (code "123") (name "unconnected-(IC3-PJ6(PCINT15)-Pad69)") (class "Default")
      (node (ref "IC3") (pin "69") (pinfunction "PJ6(PCINT15)_69") (pintype "bidirectional"))
    )
    (net (code "124") (name "unconnected-(IC3-PJ7-Pad79)") (class "Default")
      (node (ref "IC3") (pin "79") (pinfunction "PJ7_79") (pintype "bidirectional"))
    )
    (net (code "125") (name "unconnected-(IC4-(AIN0{slash}INT1)PD1-Pad7)") (class "Default")
      (node (ref "IC4") (pin "7") (pinfunction "(AIN0/INT1)PD1_7") (pintype "bidirectional"))
    )
    (net (code "126") (name "unconnected-(IC4-(AIN2{slash}PCINT11)PC2-Pad5)") (class "Default")
      (node (ref "IC4") (pin "5") (pinfunction "(AIN2/PCINT11)PC2_5") (pintype "bidirectional"))
    )
    (net (code "127") (name "unconnected-(IC4-(INT4{slash}ICP1{slash}CLK0)PC7-Pad22)") (class "Default")
      (node (ref "IC4") (pin "22") (pinfunction "(INT4/ICP1/CLK0)PC7_22") (pintype "bidirectional"))
    )
    (net (code "128") (name "unconnected-(IC4-(OC0B{slash}INT0)PD0-Pad6)") (class "Default")
      (node (ref "IC4") (pin "6") (pinfunction "(OC0B/INT0)PD0_6") (pintype "bidirectional"))
    )
    (net (code "129") (name "unconnected-(IC4-(OC1A{slash}PCINT8)PC6-Pad23)") (class "Default")
      (node (ref "IC4") (pin "23") (pinfunction "(OC1A/PCINT8)PC6_23") (pintype "bidirectional"))
    )
    (net (code "130") (name "unconnected-(IC4-(PCINT5)PB5-Pad19)") (class "Default")
      (node (ref "IC4") (pin "19") (pinfunction "(PCINT5)PB5_19") (pintype "bidirectional"))
    )
    (net (code "131") (name "unconnected-(IC4-(PCINT6)PB6-Pad20)") (class "Default")
      (node (ref "IC4") (pin "20") (pinfunction "(PCINT6)PB6_20") (pintype "bidirectional"))
    )
    (net (code "132") (name "unconnected-(IC4-(PCINT7{slash}OC0A{slash}OC1C)PB7-Pad21)") (class "Default")
      (node (ref "IC4") (pin "21") (pinfunction "(PCINT7/OC0A/OC1C)PB7_21") (pintype "bidirectional"))
    )
    (net (code "133") (name "unconnected-(IC4-(PCINT9{slash}OC1B)PC5-Pad25)") (class "Default")
      (node (ref "IC4") (pin "25") (pinfunction "(PCINT9/OC1B)PC5_25") (pintype "bidirectional"))
    )
    (net (code "134") (name "unconnected-(IC4-(PCINT10)PC4-Pad26)") (class "Default")
      (node (ref "IC4") (pin "26") (pinfunction "(PCINT10)PC4_26") (pintype "bidirectional"))
    )
    (net (code "135") (name "unconnected-(IC4-(RTS{slash}AIN5{slash}INT6)PD6-Pad12)") (class "Default")
      (node (ref "IC4") (pin "12") (pinfunction "(RTS/AIN5/INT6)PD6_12") (pintype "bidirectional"))
    )
    (net (code "136") (name "unconnected-(IC4-(SS{slash}PCINT0)PB0-Pad14)") (class "Default")
      (node (ref "IC4") (pin "14") (pinfunction "(SS/PCINT0)PB0_14") (pintype "bidirectional"))
    )
    (net (code "137") (name "unconnected-(IC4-(T1{slash}PCINT4)PB4-Pad18)") (class "Default")
      (node (ref "IC4") (pin "18") (pinfunction "(T1/PCINT4)PB4_18") (pintype "bidirectional"))
    )
    (net (code "138") (name "unconnected-(IC5A-OUT-Pad1)") (class "Default")
      (node (ref "IC5") (pin "1") (pinfunction "OUT_1") (pintype "output"))
    )
    (net (code "139") (name "unconnected-(IC6-NC{slash}FB-Pad4)") (class "Default")
      (node (ref "IC6") (pin "4") (pinfunction "NC/FB_4") (pintype "passive"))
    )
    (net (code "140") (name "unconnected-(RN1D-1-Pad4)") (class "Default")
      (node (ref "RN1") (pin "4") (pinfunction "1_4") (pintype "passive"))
    )
    (net (code "141") (name "unconnected-(RN1D-2-Pad5)") (class "Default")
      (node (ref "RN1") (pin "5") (pinfunction "2_5") (pintype "passive"))
    )
    (net (code "142") (name "unconnected-(RN2B-1-Pad2)") (class "Default")
      (node (ref "RN2") (pin "2") (pinfunction "1_2") (pintype "passive"))
    )
    (net (code "143") (name "unconnected-(RN2B-2-Pad7)") (class "Default")
      (node (ref "RN2") (pin "7") (pinfunction "2_7") (pintype "passive"))
    )
    (net (code "144") (name "unconnected-(RN2C-1-Pad3)") (class "Default")
      (node (ref "RN2") (pin "3") (pinfunction "1_3") (pintype "passive"))
    )
    (net (code "145") (name "unconnected-(RN2C-2-Pad6)") (class "Default")
      (node (ref "RN2") (pin "6") (pinfunction "2_6") (pintype "passive"))
    )
    (net (code "146") (name "unconnected-(RN3-Pad1)") (class "Default")
      (node (ref "RN3") (pin "1") (pinfunction "1_1") (pintype "passive"))
    )
    (net (code "147") (name "unconnected-(RN3A-2-Pad8)") (class "Default")
      (node (ref "RN3") (pin "8") (pinfunction "2_8") (pintype "passive"))
    )
    (net (code "148") (name "unconnected-(RN3B-1-Pad2)") (class "Default")
      (node (ref "RN3") (pin "2") (pinfunction "1_2") (pintype "passive"))
    )
    (net (code "149") (name "unconnected-(RN3B-2-Pad7)") (class "Default")
      (node (ref "RN3") (pin "7") (pinfunction "2_7") (pintype "passive"))
    )
    (net (code "150") (name "unconnected-(RN5D-1-Pad4)") (class "Default")
      (node (ref "RN5") (pin "4") (pinfunction "1_4") (pintype "passive"))
    )
    (net (code "151") (name "unconnected-(RN5D-2-Pad5)") (class "Default")
      (node (ref "RN5") (pin "5") (pinfunction "2_5") (pintype "passive"))
    )
  )
)
